# 4_LEDDRIVERS.net
KiCad netlist of a schematic drawn in Altium Designer
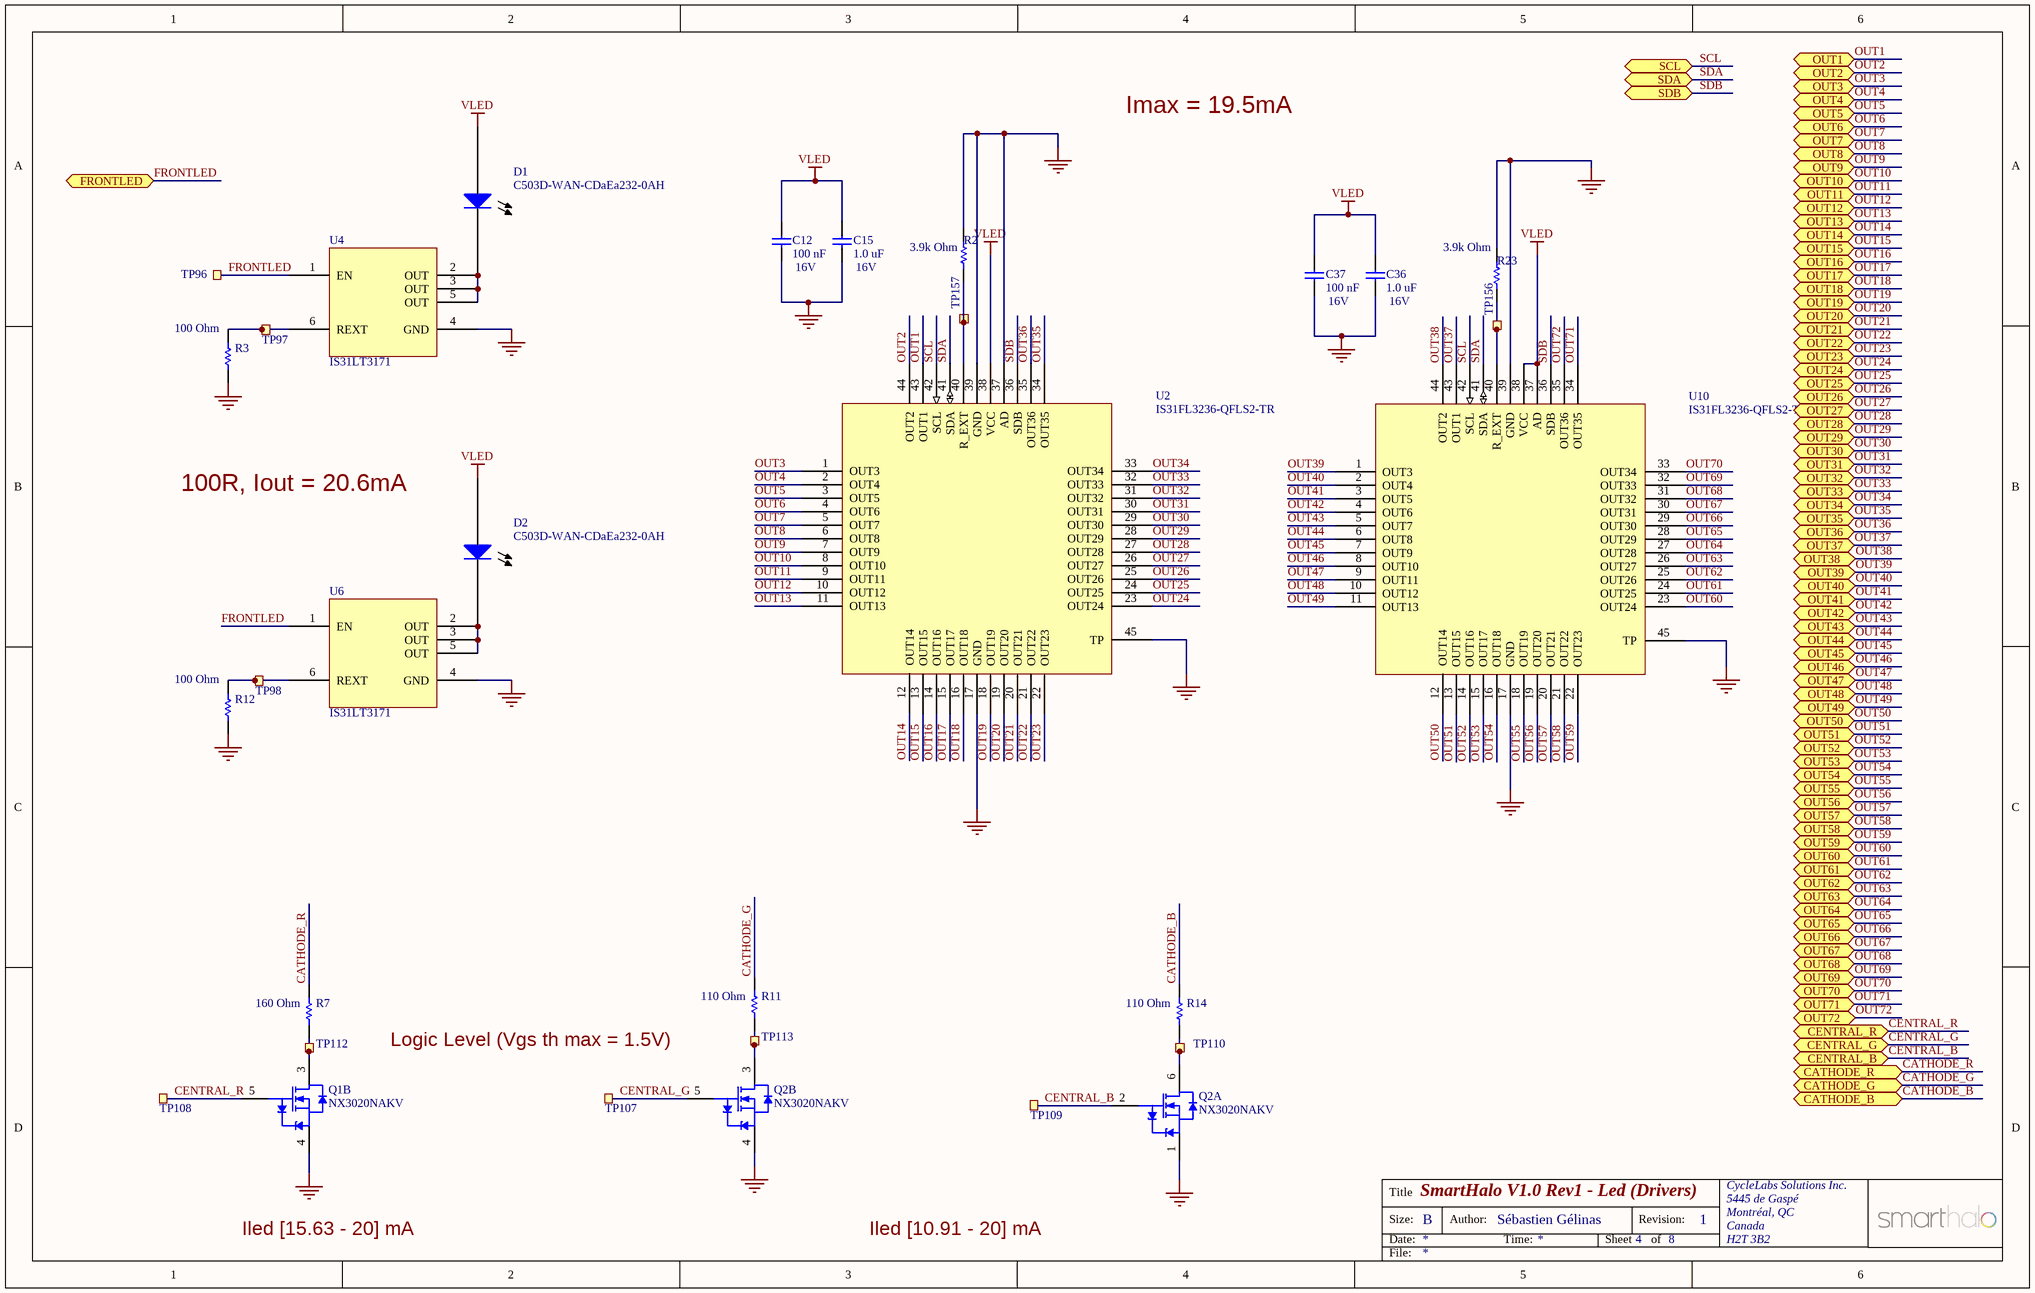
[diagram p0: 4_LEDDRIVERS.SchDoc]

(export (version "E")
  (design (tool "Eeschema 10.0.6"))
  (components
    (comp (ref "C12")
      (value "100 nF")
      (footprint "Varitron_CAP0402")
      (description "100 nF 16V X7R 10% 0402 (1005 Metric)  SMD")
      (fields
        (field (name "TOLERANCE") "10%")
        (field (name "VOLTAGE RATING") "16V")
        (field (name "MANUFACTURER") "Samsung")
      )
      (libsource (lib "SmartHalo") (part "Varitron_CAP0402"))
    )
    (comp (ref "C15")
      (value "1.0 uF")
      (footprint "Varitron_CAP0603")
      (description "1.0 uF 16V X7R 10% 0603 (1608 Metric)  SMD")
      (fields
        (field (name "TOLERANCE") "10%")
        (field (name "VOLTAGE RATING") "16V")
        (field (name "MANUFACTURER") "Samsung")
      )
      (libsource (lib "SmartHalo") (part "Varitron_CAP0603"))
    )
    (comp (ref "C36")
      (value "1.0 uF")
      (footprint "Varitron_CAP0603")
      (description "1.0 uF 16V X7R 10% 0603 (1608 Metric)  SMD")
      (fields
        (field (name "TOLERANCE") "10%")
        (field (name "VOLTAGE RATING") "16V")
        (field (name "MANUFACTURER") "Samsung")
      )
      (libsource (lib "SmartHalo") (part "Varitron_CAP0603"))
    )
    (comp (ref "C37")
      (value "100 nF")
      (footprint "Varitron_CAP0402")
      (description "100 nF 16V X7R 10% 0402 (1005 Metric)  SMD")
      (fields
        (field (name "TOLERANCE") "10%")
        (field (name "VOLTAGE RATING") "16V")
        (field (name "MANUFACTURER") "Samsung")
      )
      (libsource (lib "SmartHalo") (part "Varitron_CAP0402"))
    )
    (comp (ref "D1")
      (value "C503D-WAN-CDaEa232-0AH")
      (footprint "FRONTLED_PADS")
      (description "Cree 5mm Round LED C503D-WAN-CDaEa232-0AH")
      (fields (field (name "MANUFACTURER") "Cree") (field (name "SMARTHALO PART NUMBER") "630016-01"))
      (libsource (lib "SmartHalo") (part "C503D-WAN-CDaEa232-0AH"))
    )
    (comp (ref "D2")
      (value "C503D-WAN-CDaEa232-0AH")
      (footprint "FRONTLED_PADS")
      (description "Cree 5mm Round LED C503D-WAN-CDaEa232-0AH")
      (fields (field (name "MANUFACTURER") "Cree") (field (name "SMARTHALO PART NUMBER") "630016-01"))
      (libsource (lib "SmartHalo") (part "C503D-WAN-CDaEa232-0AH"))
    )
    (comp (ref "Q1")
      (value "NX3020NAKV")
      (footprint "SOT666")
      (description "30 V, 200 mA dual N-channel Trench MOSFET")
      (fields
        (field (name "MANUFACTURER") "NXP Semiconductors")
        (field (name "SMARTHALO PART NUMBER") "630030-01")
      )
      (libsource (lib "SmartHalo") (part "NX3020NAKV"))
    )
    (comp (ref "Q2")
      (value "NX3020NAKV")
      (footprint "SOT666")
      (description "30 V, 200 mA dual N-channel Trench MOSFET")
      (fields
        (field (name "MANUFACTURER") "NXP Semiconductors")
        (field (name "SMARTHALO PART NUMBER") "630030-01")
      )
      (libsource (lib "SmartHalo") (part "NX3020NAKV"))
    )
    (comp (ref "R2")
      (value "3.9k Ohm")
      (footprint "Varitron_RES0402")
      (description "3k9 0.063W 5%  0402 (1005 Metric)  SMD")
      (fields (field (name "TOLERANCE") "5%") (field (name "POWER") "0.063W"))
      (libsource (lib "SmartHalo") (part "Varitron_RES0402"))
    )
    (comp (ref "R3")
      (value "100 Ohm")
      (footprint "Varitron_RES0402")
      (description "100R 0.1W 5%  0402 (1005 Metric)  SMD")
      (fields (field (name "TOLERANCE") "5%") (field (name "POWER") "0.1W"))
      (libsource (lib "SmartHalo") (part "Varitron_RES0402"))
    )
    (comp (ref "R7")
      (value "160 Ohm")
      (footprint "Varitron_RES0402")
      (description "160R 0.1W 5%  0402 (1005 Metric)  SMD")
      (fields (field (name "TOLERANCE") "5%") (field (name "POWER") "0.1W"))
      (libsource (lib "SmartHalo") (part "Varitron_RES0402"))
    )
    (comp (ref "R11")
      (value "110 Ohm")
      (footprint "Varitron_RES0402")
      (description "110R 0.1W 5%  0402 (1005 Metric)  SMD")
      (fields (field (name "TOLERANCE") "5%") (field (name "POWER") "0.1W"))
      (libsource (lib "SmartHalo") (part "Varitron_RES0402"))
    )
    (comp (ref "R12")
      (value "100 Ohm")
      (footprint "Varitron_RES0402")
      (description "100R 0.1W 5%  0402 (1005 Metric)  SMD")
      (fields (field (name "TOLERANCE") "5%") (field (name "POWER") "0.1W"))
      (libsource (lib "SmartHalo") (part "Varitron_RES0402"))
    )
    (comp (ref "R14")
      (value "110 Ohm")
      (footprint "Varitron_RES0402")
      (description "110R 0.1W 5%  0402 (1005 Metric)  SMD")
      (fields (field (name "TOLERANCE") "5%") (field (name "POWER") "0.1W"))
      (libsource (lib "SmartHalo") (part "Varitron_RES0402"))
    )
    (comp (ref "R23")
      (value "3.9k Ohm")
      (footprint "Varitron_RES0402")
      (description "3k9 0.063W 5%  0402 (1005 Metric)  SMD")
      (fields (field (name "TOLERANCE") "5%") (field (name "POWER") "0.063W"))
      (libsource (lib "SmartHalo") (part "Varitron_RES0402"))
    )
    (comp (ref "TP96")
      (value "TP96")
      (footprint "TESTPAD-TH-35mils")
      (description "Testpoint, through hole, 35 mils")
      (libsource (lib "SmartHalo") (part "TESTPAD_TH_35mils"))
    )
    (comp (ref "TP97")
      (value "TP97")
      (footprint "TESTPAD-TH-35mils")
      (description "Testpoint, through hole, 35 mils")
      (libsource (lib "") (part "TESTPAD_TH_35mils_2"))
    )
    (comp (ref "TP98")
      (value "TP98")
      (footprint "TESTPAD-TH-35mils")
      (description "Testpoint, through hole, 35 mils")
      (libsource (lib "") (part "TESTPAD_TH_35mils_2"))
    )
    (comp (ref "TP107")
      (value "TP107")
      (footprint "TESTPAD-TH-35mils")
      (description "Testpoint, through hole, 35 mils")
      (libsource (lib "SmartHalo") (part "TESTPAD_TH_35mils"))
    )
    (comp (ref "TP108")
      (value "TP108")
      (footprint "TESTPAD-TH-35mils")
      (description "Testpoint, through hole, 35 mils")
      (libsource (lib "SmartHalo") (part "TESTPAD_TH_35mils"))
    )
    (comp (ref "TP109")
      (value "TP109")
      (footprint "TESTPAD-TH-35mils")
      (description "Testpoint, through hole, 35 mils")
      (libsource (lib "SmartHalo") (part "TESTPAD_TH_35mils"))
    )
    (comp (ref "TP110")
      (value "TP110")
      (footprint "TESTPAD-TH-35mils")
      (description "Testpoint, through hole, 35 mils")
      (libsource (lib "") (part "TESTPAD_TH_35mils_1"))
    )
    (comp (ref "TP112")
      (value "TP112")
      (footprint "TESTPAD-TH-35mils")
      (description "Testpoint, through hole, 35 mils")
      (libsource (lib "") (part "TESTPAD_TH_35mils_1"))
    )
    (comp (ref "TP113")
      (value "TP113")
      (footprint "TESTPAD-TH-35mils")
      (description "Testpoint, through hole, 35 mils")
      (libsource (lib "") (part "TESTPAD_TH_35mils_1"))
    )
    (comp (ref "TP156")
      (value "TP156")
      (footprint "TESTPAD-TH-35mils")
      (description "Testpoint, through hole, 35 mils")
      (libsource (lib "") (part "TESTPAD_TH_35mils_1"))
    )
    (comp (ref "TP157")
      (value "TP157")
      (footprint "TESTPAD-TH-35mils")
      (description "Testpoint, through hole, 35 mils")
      (libsource (lib "") (part "TESTPAD_TH_35mils_1"))
    )
    (comp (ref "U2")
      (value "IS31FL3236-QFLS2-TR")
      (footprint "QFN-44")
      (description "IC 36 CHANNELS LED DRIVER")
      (fields (field (name "MANUFACTURER") "ISSI") (field (name "SMARTHALO PART NUMBER") "630052-01"))
      (libsource (lib "SmartHalo") (part "IS31FL3236-QFLS2-TR"))
    )
    (comp (ref "U4")
      (value "IS31LT3171")
      (footprint "SOT23-6")
      (description "10-TO-150MA CONSTANT-CURRENT LED DRIVER")
      (fields (field (name "MANUFACTURER") "ISSI") (field (name "SMARTHALO PART NUMBER") "630054-01"))
      (libsource (lib "SmartHalo") (part "IS31LT3171"))
    )
    (comp (ref "U6")
      (value "IS31LT3171")
      (footprint "SOT23-6")
      (description "10-TO-150MA CONSTANT-CURRENT LED DRIVER")
      (fields (field (name "MANUFACTURER") "ISSI") (field (name "SMARTHALO PART NUMBER") "630054-01"))
      (libsource (lib "SmartHalo") (part "IS31LT3171"))
    )
    (comp (ref "U10")
      (value "IS31FL3236-QFLS2-TR")
      (footprint "QFN-44")
      (description "IC 36 CHANNELS LED DRIVER")
      (fields (field (name "MANUFACTURER") "ISSI") (field (name "SMARTHALO PART NUMBER") "630052-01"))
      (libsource (lib "SmartHalo") (part "IS31FL3236-QFLS2-TR"))
    )
  )
  (nets
    (net (code "1") (name "/CATHODE_B") (class "Default")
      (node (ref "R14") (pin "2") (pinfunction "2_2") (pintype "passive"))
    )
    (net (code "2") (name "/CATHODE_G") (class "Default")
      (node (ref "R11") (pin "2") (pinfunction "2_2") (pintype "passive"))
    )
    (net (code "3") (name "/CATHODE_R") (class "Default")
      (node (ref "R7") (pin "2") (pinfunction "2_2") (pintype "passive"))
    )
    (net (code "4") (name "/CENTRAL_B") (class "Default")
      (node (ref "Q2") (pin "2") (pinfunction "G1_2") (pintype "passive"))
      (node (ref "TP109") (pin "1") (pinfunction "1_1") (pintype "passive"))
    )
    (net (code "5") (name "/CENTRAL_G") (class "Default")
      (node (ref "Q2") (pin "5") (pinfunction "G2_5") (pintype "passive"))
      (node (ref "TP107") (pin "1") (pinfunction "1_1") (pintype "passive"))
    )
    (net (code "6") (name "/CENTRAL_R") (class "Default")
      (node (ref "Q1") (pin "5") (pinfunction "G2_5") (pintype "passive"))
      (node (ref "TP108") (pin "1") (pinfunction "1_1") (pintype "passive"))
    )
    (net (code "7") (name "/FRONTLED") (class "Default")
      (node (ref "TP96") (pin "1") (pinfunction "1_1") (pintype "passive"))
      (node (ref "U4") (pin "1") (pinfunction "EN_1") (pintype "passive"))
      (node (ref "U6") (pin "1") (pinfunction "EN_1") (pintype "passive"))
    )
    (net (code "8") (name "/OUT1") (class "Default")
      (node (ref "U2") (pin "43") (pinfunction "OUT1_43") (pintype "passive"))
    )
    (net (code "9") (name "/OUT2") (class "Default")
      (node (ref "U2") (pin "44") (pinfunction "OUT2_44") (pintype "passive"))
    )
    (net (code "10") (name "/OUT3") (class "Default")
      (node (ref "U2") (pin "1") (pinfunction "OUT3_1") (pintype "passive"))
    )
    (net (code "11") (name "/OUT4") (class "Default")
      (node (ref "U2") (pin "2") (pinfunction "OUT4_2") (pintype "passive"))
    )
    (net (code "12") (name "/OUT5") (class "Default")
      (node (ref "U2") (pin "3") (pinfunction "OUT5_3") (pintype "passive"))
    )
    (net (code "13") (name "/OUT6") (class "Default")
      (node (ref "U2") (pin "4") (pinfunction "OUT6_4") (pintype "passive"))
    )
    (net (code "14") (name "/OUT7") (class "Default")
      (node (ref "U2") (pin "5") (pinfunction "OUT7_5") (pintype "passive"))
    )
    (net (code "15") (name "/OUT8") (class "Default")
      (node (ref "U2") (pin "6") (pinfunction "OUT8_6") (pintype "passive"))
    )
    (net (code "16") (name "/OUT9") (class "Default")
      (node (ref "U2") (pin "7") (pinfunction "OUT9_7") (pintype "passive"))
    )
    (net (code "17") (name "/OUT10") (class "Default")
      (node (ref "U2") (pin "8") (pinfunction "OUT10_8") (pintype "passive"))
    )
    (net (code "18") (name "/OUT11") (class "Default")
      (node (ref "U2") (pin "9") (pinfunction "OUT11_9") (pintype "passive"))
    )
    (net (code "19") (name "/OUT12") (class "Default")
      (node (ref "U2") (pin "10") (pinfunction "OUT12_10") (pintype "passive"))
    )
    (net (code "20") (name "/OUT13") (class "Default")
      (node (ref "U2") (pin "11") (pinfunction "OUT13_11") (pintype "passive"))
    )
    (net (code "21") (name "/OUT14") (class "Default")
      (node (ref "U2") (pin "12") (pinfunction "OUT14_12") (pintype "passive"))
    )
    (net (code "22") (name "/OUT15") (class "Default")
      (node (ref "U2") (pin "13") (pinfunction "OUT15_13") (pintype "passive"))
    )
    (net (code "23") (name "/OUT16") (class "Default")
      (node (ref "U2") (pin "14") (pinfunction "OUT16_14") (pintype "passive"))
    )
    (net (code "24") (name "/OUT17") (class "Default")
      (node (ref "U2") (pin "15") (pinfunction "OUT17_15") (pintype "passive"))
    )
    (net (code "25") (name "/OUT18") (class "Default")
      (node (ref "U2") (pin "16") (pinfunction "OUT18_16") (pintype "passive"))
    )
    (net (code "26") (name "/OUT19") (class "Default")
      (node (ref "U2") (pin "18") (pinfunction "OUT19_18") (pintype "passive"))
    )
    (net (code "27") (name "/OUT20") (class "Default")
      (node (ref "U2") (pin "19") (pinfunction "OUT20_19") (pintype "passive"))
    )
    (net (code "28") (name "/OUT21") (class "Default")
      (node (ref "U2") (pin "20") (pinfunction "OUT21_20") (pintype "passive"))
    )
    (net (code "29") (name "/OUT22") (class "Default")
      (node (ref "U2") (pin "21") (pinfunction "OUT22_21") (pintype "passive"))
    )
    (net (code "30") (name "/OUT23") (class "Default")
      (node (ref "U2") (pin "22") (pinfunction "OUT23_22") (pintype "passive"))
    )
    (net (code "31") (name "/OUT24") (class "Default")
      (node (ref "U2") (pin "23") (pinfunction "OUT24_23") (pintype "passive"))
    )
    (net (code "32") (name "/OUT25") (class "Default")
      (node (ref "U2") (pin "24") (pinfunction "OUT25_24") (pintype "passive"))
    )
    (net (code "33") (name "/OUT26") (class "Default")
      (node (ref "U2") (pin "25") (pinfunction "OUT26_25") (pintype "passive"))
    )
    (net (code "34") (name "/OUT27") (class "Default")
      (node (ref "U2") (pin "26") (pinfunction "OUT27_26") (pintype "passive"))
    )
    (net (code "35") (name "/OUT28") (class "Default")
      (node (ref "U2") (pin "27") (pinfunction "OUT28_27") (pintype "passive"))
    )
    (net (code "36") (name "/OUT29") (class "Default")
      (node (ref "U2") (pin "28") (pinfunction "OUT29_28") (pintype "passive"))
    )
    (net (code "37") (name "/OUT30") (class "Default")
      (node (ref "U2") (pin "29") (pinfunction "OUT30_29") (pintype "passive"))
    )
    (net (code "38") (name "/OUT31") (class "Default")
      (node (ref "U2") (pin "30") (pinfunction "OUT31_30") (pintype "passive"))
    )
    (net (code "39") (name "/OUT32") (class "Default")
      (node (ref "U2") (pin "31") (pinfunction "OUT32_31") (pintype "passive"))
    )
    (net (code "40") (name "/OUT33") (class "Default")
      (node (ref "U2") (pin "32") (pinfunction "OUT33_32") (pintype "passive"))
    )
    (net (code "41") (name "/OUT34") (class "Default")
      (node (ref "U2") (pin "33") (pinfunction "OUT34_33") (pintype "passive"))
    )
    (net (code "42") (name "/OUT35") (class "Default")
      (node (ref "U2") (pin "34") (pinfunction "OUT35_34") (pintype "passive"))
    )
    (net (code "43") (name "/OUT36") (class "Default")
      (node (ref "U2") (pin "35") (pinfunction "OUT36_35") (pintype "passive"))
    )
    (net (code "44") (name "/OUT37") (class "Default")
      (node (ref "U10") (pin "43") (pinfunction "OUT1_43") (pintype "passive"))
    )
    (net (code "45") (name "/OUT38") (class "Default")
      (node (ref "U10") (pin "44") (pinfunction "OUT2_44") (pintype "passive"))
    )
    (net (code "46") (name "/OUT39") (class "Default")
      (node (ref "U10") (pin "1") (pinfunction "OUT3_1") (pintype "passive"))
    )
    (net (code "47") (name "/OUT40") (class "Default")
      (node (ref "U10") (pin "2") (pinfunction "OUT4_2") (pintype "passive"))
    )
    (net (code "48") (name "/OUT41") (class "Default")
      (node (ref "U10") (pin "3") (pinfunction "OUT5_3") (pintype "passive"))
    )
    (net (code "49") (name "/OUT42") (class "Default")
      (node (ref "U10") (pin "4") (pinfunction "OUT6_4") (pintype "passive"))
    )
    (net (code "50") (name "/OUT43") (class "Default")
      (node (ref "U10") (pin "5") (pinfunction "OUT7_5") (pintype "passive"))
    )
    (net (code "51") (name "/OUT44") (class "Default")
      (node (ref "U10") (pin "6") (pinfunction "OUT8_6") (pintype "passive"))
    )
    (net (code "52") (name "/OUT45") (class "Default")
      (node (ref "U10") (pin "7") (pinfunction "OUT9_7") (pintype "passive"))
    )
    (net (code "53") (name "/OUT46") (class "Default")
      (node (ref "U10") (pin "8") (pinfunction "OUT10_8") (pintype "passive"))
    )
    (net (code "54") (name "/OUT47") (class "Default")
      (node (ref "U10") (pin "9") (pinfunction "OUT11_9") (pintype "passive"))
    )
    (net (code "55") (name "/OUT48") (class "Default")
      (node (ref "U10") (pin "10") (pinfunction "OUT12_10") (pintype "passive"))
    )
    (net (code "56") (name "/OUT49") (class "Default")
      (node (ref "U10") (pin "11") (pinfunction "OUT13_11") (pintype "passive"))
    )
    (net (code "57") (name "/OUT50") (class "Default")
      (node (ref "U10") (pin "12") (pinfunction "OUT14_12") (pintype "passive"))
    )
    (net (code "58") (name "/OUT51") (class "Default")
      (node (ref "U10") (pin "13") (pinfunction "OUT15_13") (pintype "passive"))
    )
    (net (code "59") (name "/OUT52") (class "Default")
      (node (ref "U10") (pin "14") (pinfunction "OUT16_14") (pintype "passive"))
    )
    (net (code "60") (name "/OUT53") (class "Default")
      (node (ref "U10") (pin "15") (pinfunction "OUT17_15") (pintype "passive"))
    )
    (net (code "61") (name "/OUT54") (class "Default")
      (node (ref "U10") (pin "16") (pinfunction "OUT18_16") (pintype "passive"))
    )
    (net (code "62") (name "/OUT55") (class "Default")
      (node (ref "U10") (pin "18") (pinfunction "OUT19_18") (pintype "passive"))
    )
    (net (code "63") (name "/OUT56") (class "Default")
      (node (ref "U10") (pin "19") (pinfunction "OUT20_19") (pintype "passive"))
    )
    (net (code "64") (name "/OUT57") (class "Default")
      (node (ref "U10") (pin "20") (pinfunction "OUT21_20") (pintype "passive"))
    )
    (net (code "65") (name "/OUT58") (class "Default")
      (node (ref "U10") (pin "21") (pinfunction "OUT22_21") (pintype "passive"))
    )
    (net (code "66") (name "/OUT59") (class "Default")
      (node (ref "U10") (pin "22") (pinfunction "OUT23_22") (pintype "passive"))
    )
    (net (code "67") (name "/OUT60") (class "Default")
      (node (ref "U10") (pin "23") (pinfunction "OUT24_23") (pintype "passive"))
    )
    (net (code "68") (name "/OUT61") (class "Default")
      (node (ref "U10") (pin "24") (pinfunction "OUT25_24") (pintype "passive"))
    )
    (net (code "69") (name "/OUT62") (class "Default")
      (node (ref "U10") (pin "25") (pinfunction "OUT26_25") (pintype "passive"))
    )
    (net (code "70") (name "/OUT63") (class "Default")
      (node (ref "U10") (pin "26") (pinfunction "OUT27_26") (pintype "passive"))
    )
    (net (code "71") (name "/OUT64") (class "Default")
      (node (ref "U10") (pin "27") (pinfunction "OUT28_27") (pintype "passive"))
    )
    (net (code "72") (name "/OUT65") (class "Default")
      (node (ref "U10") (pin "28") (pinfunction "OUT29_28") (pintype "passive"))
    )
    (net (code "73") (name "/OUT66") (class "Default")
      (node (ref "U10") (pin "29") (pinfunction "OUT30_29") (pintype "passive"))
    )
    (net (code "74") (name "/OUT67") (class "Default")
      (node (ref "U10") (pin "30") (pinfunction "OUT31_30") (pintype "passive"))
    )
    (net (code "75") (name "/OUT68") (class "Default")
      (node (ref "U10") (pin "31") (pinfunction "OUT32_31") (pintype "passive"))
    )
    (net (code "76") (name "/OUT69") (class "Default")
      (node (ref "U10") (pin "32") (pinfunction "OUT33_32") (pintype "passive"))
    )
    (net (code "77") (name "/OUT70") (class "Default")
      (node (ref "U10") (pin "33") (pinfunction "OUT34_33") (pintype "passive"))
    )
    (net (code "78") (name "/OUT71") (class "Default")
      (node (ref "U10") (pin "34") (pinfunction "OUT35_34") (pintype "passive"))
    )
    (net (code "79") (name "/OUT72") (class "Default")
      (node (ref "U10") (pin "35") (pinfunction "OUT36_35") (pintype "passive"))
    )
    (net (code "80") (name "/SCL") (class "Default")
      (node (ref "U10") (pin "42") (pinfunction "SCL_42") (pintype "input"))
      (node (ref "U2") (pin "42") (pinfunction "SCL_42") (pintype "input"))
    )
    (net (code "81") (name "/SDA") (class "Default")
      (node (ref "U10") (pin "41") (pinfunction "SDA_41") (pintype "bidirectional"))
      (node (ref "U2") (pin "41") (pinfunction "SDA_41") (pintype "bidirectional"))
    )
    (net (code "82") (name "/SDB") (class "Default")
      (node (ref "U10") (pin "36") (pinfunction "SDB_36") (pintype "passive"))
      (node (ref "U2") (pin "36") (pinfunction "SDB_36") (pintype "passive"))
    )
    (net (code "83") (name "GND") (class "Default")
      (node (ref "C12") (pin "2") (pinfunction "2_2") (pintype "passive"))
      (node (ref "C15") (pin "2") (pinfunction "2_2") (pintype "passive"))
      (node (ref "C36") (pin "2") (pinfunction "2_2") (pintype "passive"))
      (node (ref "C37") (pin "2") (pinfunction "2_2") (pintype "passive"))
      (node (ref "Q1") (pin "4") (pinfunction "S2_4") (pintype "passive"))
      (node (ref "Q2") (pin "1") (pinfunction "S1_1") (pintype "passive"))
      (node (ref "Q2") (pin "4") (pinfunction "S2_4") (pintype "passive"))
      (node (ref "R12") (pin "1") (pinfunction "1_1") (pintype "passive"))
      (node (ref "R2") (pin "2") (pinfunction "2_2") (pintype "passive"))
      (node (ref "R23") (pin "2") (pinfunction "2_2") (pintype "passive"))
      (node (ref "R3") (pin "1") (pinfunction "1_1") (pintype "passive"))
      (node (ref "U10") (pin "17") (pinfunction "GND_17") (pintype "power_in"))
      (node (ref "U10") (pin "39") (pinfunction "GND_39") (pintype "power_in"))
      (node (ref "U10") (pin "45") (pinfunction "TP_45") (pintype "power_in"))
      (node (ref "U2") (pin "17") (pinfunction "GND_17") (pintype "power_in"))
      (node (ref "U2") (pin "37") (pinfunction "AD_37") (pintype "passive"))
      (node (ref "U2") (pin "39") (pinfunction "GND_39") (pintype "power_in"))
      (node (ref "U2") (pin "45") (pinfunction "TP_45") (pintype "power_in"))
      (node (ref "U4") (pin "4") (pinfunction "GND_4") (pintype "passive"))
      (node (ref "U6") (pin "4") (pinfunction "GND_4") (pintype "passive"))
    )
    (net (code "84") (name "Net-(D1-Cathode)") (class "Default")
      (node (ref "D1") (pin "2") (pinfunction "Cathode_2") (pintype "passive"))
      (node (ref "U4") (pin "2") (pinfunction "OUT_2") (pintype "passive"))
      (node (ref "U4") (pin "3") (pinfunction "OUT_3") (pintype "passive"))
      (node (ref "U4") (pin "5") (pinfunction "OUT_5") (pintype "passive"))
    )
    (net (code "85") (name "Net-(D2-Cathode)") (class "Default")
      (node (ref "D2") (pin "2") (pinfunction "Cathode_2") (pintype "passive"))
      (node (ref "U6") (pin "2") (pinfunction "OUT_2") (pintype "passive"))
      (node (ref "U6") (pin "3") (pinfunction "OUT_3") (pintype "passive"))
      (node (ref "U6") (pin "5") (pinfunction "OUT_5") (pintype "passive"))
    )
    (net (code "86") (name "Net-(Q1B-D2)") (class "Default")
      (node (ref "Q1") (pin "3") (pinfunction "D2_3") (pintype "passive"))
      (node (ref "R7") (pin "1") (pinfunction "1_1") (pintype "passive"))
      (node (ref "TP112") (pin "1") (pinfunction "1_1") (pintype "passive"))
    )
    (net (code "87") (name "Net-(Q2A-D1)") (class "Default")
      (node (ref "Q2") (pin "6") (pinfunction "D1_6") (pintype "passive"))
      (node (ref "R14") (pin "1") (pinfunction "1_1") (pintype "passive"))
      (node (ref "TP110") (pin "1") (pinfunction "1_1") (pintype "passive"))
    )
    (net (code "88") (name "Net-(Q2B-D2)") (class "Default")
      (node (ref "Q2") (pin "3") (pinfunction "D2_3") (pintype "passive"))
      (node (ref "R11") (pin "1") (pinfunction "1_1") (pintype "passive"))
      (node (ref "TP113") (pin "1") (pinfunction "1_1") (pintype "passive"))
    )
    (net (code "89") (name "Net-(U2-R_EXT)") (class "Default")
      (node (ref "R2") (pin "1") (pinfunction "1_1") (pintype "passive"))
      (node (ref "TP157") (pin "1") (pinfunction "1_1") (pintype "passive"))
      (node (ref "U2") (pin "40") (pinfunction "R_EXT_40") (pintype "passive"))
    )
    (net (code "90") (name "Net-(U4-REXT)") (class "Default")
      (node (ref "R3") (pin "2") (pinfunction "2_2") (pintype "passive"))
      (node (ref "TP97") (pin "1") (pinfunction "1_1") (pintype "passive"))
      (node (ref "U4") (pin "6") (pinfunction "REXT_6") (pintype "passive"))
    )
    (net (code "91") (name "Net-(U6-REXT)") (class "Default")
      (node (ref "R12") (pin "2") (pinfunction "2_2") (pintype "passive"))
      (node (ref "TP98") (pin "1") (pinfunction "1_1") (pintype "passive"))
      (node (ref "U6") (pin "6") (pinfunction "REXT_6") (pintype "passive"))
    )
    (net (code "92") (name "Net-(U10-R_EXT)") (class "Default")
      (node (ref "R23") (pin "1") (pinfunction "1_1") (pintype "passive"))
      (node (ref "TP156") (pin "1") (pinfunction "1_1") (pintype "passive"))
      (node (ref "U10") (pin "40") (pinfunction "R_EXT_40") (pintype "passive"))
    )
    (net (code "93") (name "VLED") (class "Default")
      (node (ref "C12") (pin "1") (pinfunction "1_1") (pintype "passive"))
      (node (ref "C15") (pin "1") (pinfunction "1_1") (pintype "passive"))
      (node (ref "C36") (pin "1") (pinfunction "1_1") (pintype "passive"))
      (node (ref "C37") (pin "1") (pinfunction "1_1") (pintype "passive"))
      (node (ref "D1") (pin "1") (pinfunction "Anode_1") (pintype "passive"))
      (node (ref "D2") (pin "1") (pinfunction "Anode_1") (pintype "passive"))
      (node (ref "U10") (pin "37") (pinfunction "AD_37") (pintype "passive"))
      (node (ref "U10") (pin "38") (pinfunction "VCC_38") (pintype "power_in"))
      (node (ref "U2") (pin "38") (pinfunction "VCC_38") (pintype "power_in"))
    )
  )
)
